# supply.net
KiCad netlist of a schematic drawn in Altium Designer
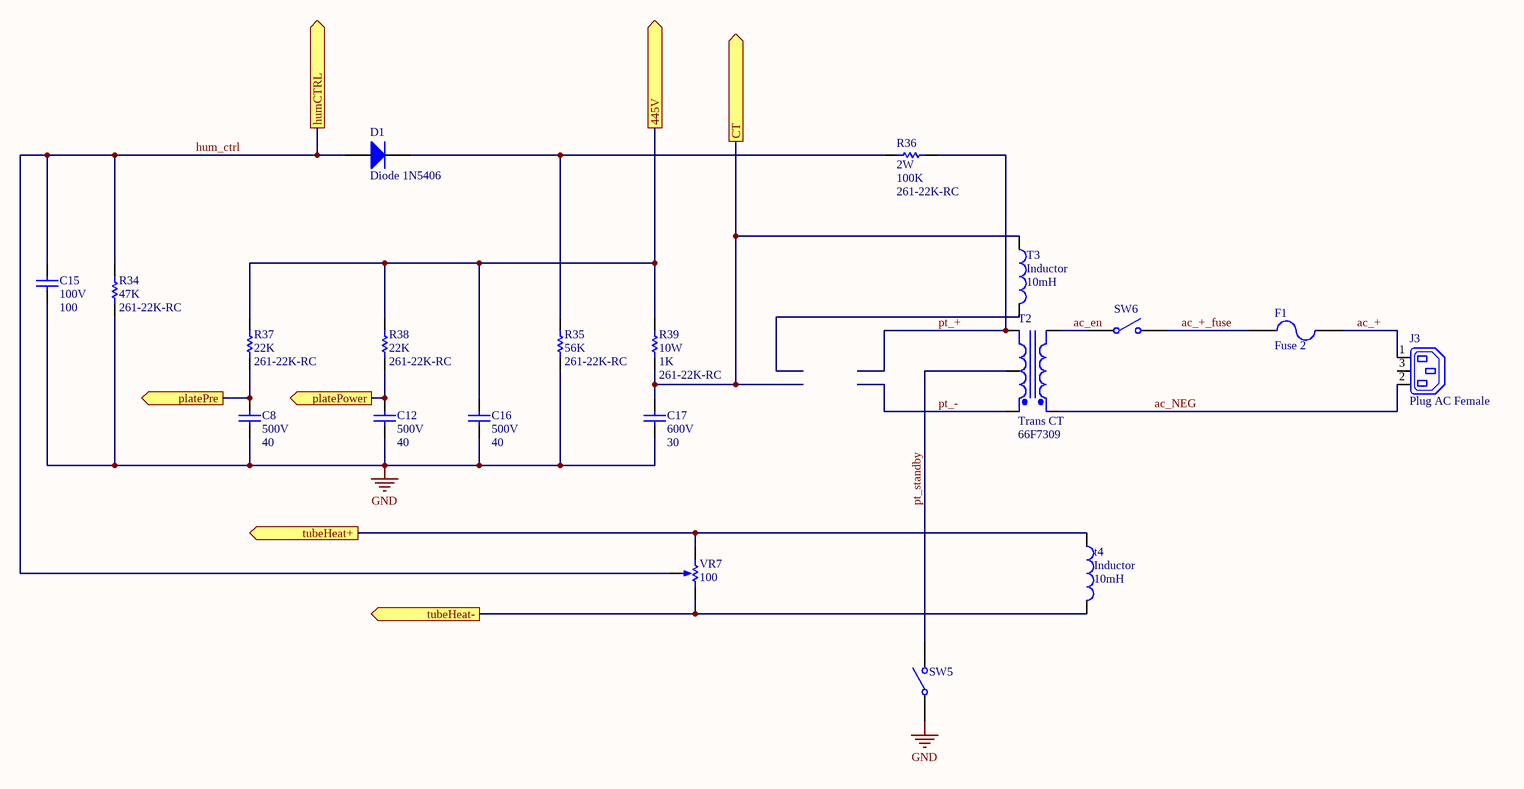
[diagram p0: supply.SchDoc]

(export (version "E")
  (design (tool "Eeschema 10.0.6"))
  (components
    (comp (ref "C8")
      (value "500V")
      (footprint "RAD-0.3")
      (description "Capacitor")
      (fields (field (name "ALTIUM_VALUE") "40") (field (name "PUBLISHER") "Altium Limited"))
      (libsource (lib "Miscellaneous Devices") (part "Cap"))
    )
    (comp (ref "C12")
      (value "500V")
      (footprint "RAD-0.3")
      (description "Capacitor")
      (fields (field (name "ALTIUM_VALUE") "40") (field (name "PUBLISHER") "Altium Limited"))
      (libsource (lib "Miscellaneous Devices") (part "Cap"))
    )
    (comp (ref "C15")
      (value "100V")
      (footprint "RAD-0.3")
      (description "Capacitor")
      (fields (field (name "ALTIUM_VALUE") "100") (field (name "PUBLISHER") "Altium Limited"))
      (libsource (lib "Miscellaneous Devices") (part "Cap"))
    )
    (comp (ref "C16")
      (value "500V")
      (footprint "RAD-0.3")
      (description "Capacitor")
      (fields (field (name "ALTIUM_VALUE") "40") (field (name "PUBLISHER") "Altium Limited"))
      (libsource (lib "Miscellaneous Devices") (part "Cap"))
    )
    (comp (ref "C17")
      (value "600V")
      (footprint "RAD-0.3")
      (description "Capacitor")
      (fields (field (name "ALTIUM_VALUE") "30") (field (name "PUBLISHER") "Altium Limited"))
      (libsource (lib "Miscellaneous Devices") (part "Cap"))
    )
    (comp (ref "D1")
      (value "Diode 1N5406")
      (footprint "DO-201AD")
      (description "3 Amp General Purpose Rectifier")
      (fields (field (name "PUBLISHER") "Altium Limited"))
      (libsource (lib "Miscellaneous Devices") (part "Diode 1N5406"))
    )
    (comp (ref "F1")
      (value "Fuse 2")
      (footprint "PIN-W2/E2.8")
      (description "Fuse")
      (fields (field (name "PUBLISHER") "Altium Limited"))
      (libsource (lib "Miscellaneous Devices") (part "Fuse 2"))
    )
    (comp (ref "J3")
      (value "Plug AC Female")
      (footprint "IEC7-2H3")
      (description "IEC Mains Power Outlet, EN60 320-2-2 F Class I, PC Flange Rear Mount, Chassis Socket")
      (fields (field (name "PUBLISHER") "Altium Limited"))
      (libsource (lib "Miscellaneous Connectors") (part "Plug AC Female"))
    )
    (comp (ref "R34")
      (value "47K")
      (footprint "AXIAL-0.3")
      (description "Resistor")
      (fields
        (field (name "SUPPLIER PART NUMBER 1") "261-22K-RC")
        (field (name "Comment") "Res1")
        (field (name "PUBLISHER") "Altium Limited")
      )
      (libsource (lib "Miscellaneous Devices") (part "Res1"))
    )
    (comp (ref "R35")
      (value "56K")
      (footprint "AXIAL-0.3")
      (description "Resistor")
      (fields
        (field (name "SUPPLIER PART NUMBER 1") "261-22K-RC")
        (field (name "Comment") "Res1")
        (field (name "PUBLISHER") "Altium Limited")
      )
      (libsource (lib "Miscellaneous Devices") (part "Res1"))
    )
    (comp (ref "R36")
      (value "2W")
      (footprint "AXIAL-0.3")
      (description "Resistor")
      (fields
        (field (name "ALTIUM_VALUE") "100K")
        (field (name "SUPPLIER PART NUMBER 1") "261-22K-RC")
        (field (name "PUBLISHER") "Altium Limited")
      )
      (libsource (lib "Miscellaneous Devices") (part "Res1"))
    )
    (comp (ref "R37")
      (value "22K")
      (footprint "AXIAL-0.3")
      (description "Resistor")
      (fields
        (field (name "SUPPLIER PART NUMBER 1") "261-22K-RC")
        (field (name "Comment") "Res1")
        (field (name "PUBLISHER") "Altium Limited")
      )
      (libsource (lib "Miscellaneous Devices") (part "Res1"))
    )
    (comp (ref "R38")
      (value "22K")
      (footprint "AXIAL-0.3")
      (description "Resistor")
      (fields
        (field (name "SUPPLIER PART NUMBER 1") "261-22K-RC")
        (field (name "Comment") "Res1")
        (field (name "PUBLISHER") "Altium Limited")
      )
      (libsource (lib "Miscellaneous Devices") (part "Res1"))
    )
    (comp (ref "R39")
      (value "10W")
      (footprint "AXIAL-0.3")
      (description "Resistor")
      (fields
        (field (name "ALTIUM_VALUE") "1K")
        (field (name "SUPPLIER PART NUMBER 1") "261-22K-RC")
        (field (name "PUBLISHER") "Altium Limited")
      )
      (libsource (lib "Miscellaneous Devices") (part "Res1"))
    )
    (comp (ref "SW5")
      (value "SW-SPST")
      (footprint "SPST-2")
      (description "Single-Pole, Single-Throw Switch")
      (fields (field (name "PUBLISHER") "Altium Limited"))
      (libsource (lib "Miscellaneous Devices") (part "SW-SPST"))
    )
    (comp (ref "SW6")
      (value "SW-SPST")
      (footprint "SPST-2")
      (description "Single-Pole, Single-Throw Switch")
      (fields (field (name "PUBLISHER") "Altium Limited"))
      (libsource (lib "Miscellaneous Devices") (part "SW-SPST"))
    )
    (comp (ref "T2")
      (value "Trans CT")
      (footprint "HDR1X5")
      (description "Center-Tapped Transformer (Coupled Inductor Model)")
      (fields (field (name "SUPPLIER PART NUMBER 1") "66F7309") (field (name "PUBLISHER") "Altium Limited"))
      (libsource (lib "Miscellaneous Devices") (part "Trans CT"))
    )
    (comp (ref "T3")
      (value "Inductor")
      (footprint "HDR1X2")
      (fields (field (name "ALTIUM_VALUE") "10mH") (field (name "PUBLISHER") "Altium Limited"))
      (libsource (lib "Miscellaneous Devices") (part "Inductor"))
    )
    (comp (ref "t4")
      (value "Inductor")
      (footprint "HDR1X2")
      (fields (field (name "ALTIUM_VALUE") "10mH") (field (name "PUBLISHER") "Altium Limited"))
      (libsource (lib "Miscellaneous Devices") (part "Inductor"))
    )
    (comp (ref "VR7")
      (value "100")
      (footprint "VR5")
      (description "Potentiometer")
      (fields (field (name "Comment") "RPot") (field (name "PUBLISHER") "Altium Limited"))
      (libsource (lib "Miscellaneous Devices") (part "RPot"))
    )
  )
  (nets
    (net (code "1") (name "/445V") (class "Default")
      (node (ref "C16") (pin "2") (pinfunction "2_2") (pintype "passive"))
      (node (ref "R37") (pin "2") (pinfunction "2_2") (pintype "passive"))
      (node (ref "R38") (pin "2") (pinfunction "2_2") (pintype "passive"))
      (node (ref "R39") (pin "2") (pinfunction "2_2") (pintype "passive"))
    )
    (net (code "2") (name "/CT") (class "Default")
      (node (ref "C17") (pin "2") (pinfunction "2_2") (pintype "passive"))
      (node (ref "R39") (pin "1") (pinfunction "1_1") (pintype "passive"))
      (node (ref "T3") (pin "1") (pinfunction "1_1") (pintype "passive"))
    )
    (net (code "3") (name "/ac_+") (class "Default")
      (node (ref "F1") (pin "2") (pinfunction "2_2") (pintype "passive"))
      (node (ref "J3") (pin "1") (pinfunction "L_1") (pintype "power_in"))
    )
    (net (code "4") (name "/ac_+_fuse") (class "Default")
      (node (ref "F1") (pin "1") (pinfunction "1_1") (pintype "passive"))
      (node (ref "SW6") (pin "2") (pinfunction "NO_2") (pintype "passive"))
    )
    (net (code "5") (name "/ac_NEG") (class "Default")
      (node (ref "J3") (pin "2") (pinfunction "N_2") (pintype "power_in"))
      (node (ref "T2") (pin "1") (pinfunction "Pri+_1") (pintype "passive"))
    )
    (net (code "6") (name "/ac_en") (class "Default")
      (node (ref "SW6") (pin "1") (pinfunction "COMMON_1") (pintype "passive"))
      (node (ref "T2") (pin "2") (pinfunction "Pri-_2") (pintype "passive"))
    )
    (net (code "7") (name "/hum_ctrl") (class "Default")
      (node (ref "C15") (pin "2") (pinfunction "2_2") (pintype "passive"))
      (node (ref "D1") (pin "1") (pinfunction "A_1") (pintype "passive"))
      (node (ref "R34") (pin "2") (pinfunction "2_2") (pintype "passive"))
      (node (ref "VR7") (pin "3") (pinfunction "TAP_3") (pintype "passive"))
    )
    (net (code "8") (name "/platePower") (class "Default")
      (node (ref "C12") (pin "2") (pinfunction "2_2") (pintype "passive"))
      (node (ref "R38") (pin "1") (pinfunction "1_1") (pintype "passive"))
    )
    (net (code "9") (name "/platePre") (class "Default")
      (node (ref "C8") (pin "2") (pinfunction "2_2") (pintype "passive"))
      (node (ref "R37") (pin "1") (pinfunction "1_1") (pintype "passive"))
    )
    (net (code "10") (name "/pt_+") (class "Default")
      (node (ref "R36") (pin "1") (pinfunction "1_1") (pintype "passive"))
      (node (ref "T2") (pin "5") (pinfunction "Sec-_5") (pintype "passive"))
    )
    (net (code "11") (name "/pt_-") (class "Default")
      (node (ref "T2") (pin "3") (pinfunction "Sec+_3") (pintype "passive"))
    )
    (net (code "12") (name "/pt_standby") (class "Default")
      (node (ref "SW5") (pin "2") (pinfunction "NO_2") (pintype "passive"))
      (node (ref "T2") (pin "4") (pinfunction "SecCT_4") (pintype "passive"))
    )
    (net (code "13") (name "/tubeHeat+") (class "Default")
      (node (ref "VR7") (pin "1") (pinfunction "TOP_1") (pintype "passive"))
      (node (ref "t4") (pin "1") (pinfunction "1_1") (pintype "passive"))
    )
    (net (code "14") (name "/tubeHeat-") (class "Default")
      (node (ref "VR7") (pin "2") (pinfunction "BOT_2") (pintype "passive"))
      (node (ref "t4") (pin "2") (pinfunction "2_2") (pintype "passive"))
    )
    (net (code "15") (name "GND") (class "Default")
      (node (ref "C12") (pin "1") (pinfunction "1_1") (pintype "passive"))
      (node (ref "C15") (pin "1") (pinfunction "1_1") (pintype "passive"))
      (node (ref "C16") (pin "1") (pinfunction "1_1") (pintype "passive"))
      (node (ref "C17") (pin "1") (pinfunction "1_1") (pintype "passive"))
      (node (ref "C8") (pin "1") (pinfunction "1_1") (pintype "passive"))
      (node (ref "R34") (pin "1") (pinfunction "1_1") (pintype "passive"))
      (node (ref "R35") (pin "1") (pinfunction "1_1") (pintype "passive"))
      (node (ref "SW5") (pin "1") (pinfunction "COMMON_1") (pintype "passive"))
    )
    (net (code "16") (name "Net-(D1-K)") (class "Default")
      (node (ref "D1") (pin "2") (pinfunction "K_2") (pintype "passive"))
      (node (ref "R35") (pin "2") (pinfunction "2_2") (pintype "passive"))
      (node (ref "R36") (pin "2") (pinfunction "2_2") (pintype "passive"))
    )
    (net (code "17") (name "unconnected-(J3-E-Pad3)") (class "Default")
      (node (ref "J3") (pin "3") (pinfunction "E_3") (pintype "power_in"))
    )
    (net (code "18") (name "unconnected-(T3-Pad2)") (class "Default")
      (node (ref "T3") (pin "2") (pinfunction "2_2") (pintype "passive"))
    )
  )
)
